# royer_DBD.net
KiCad netlist of a schematic drawn in EAGLE
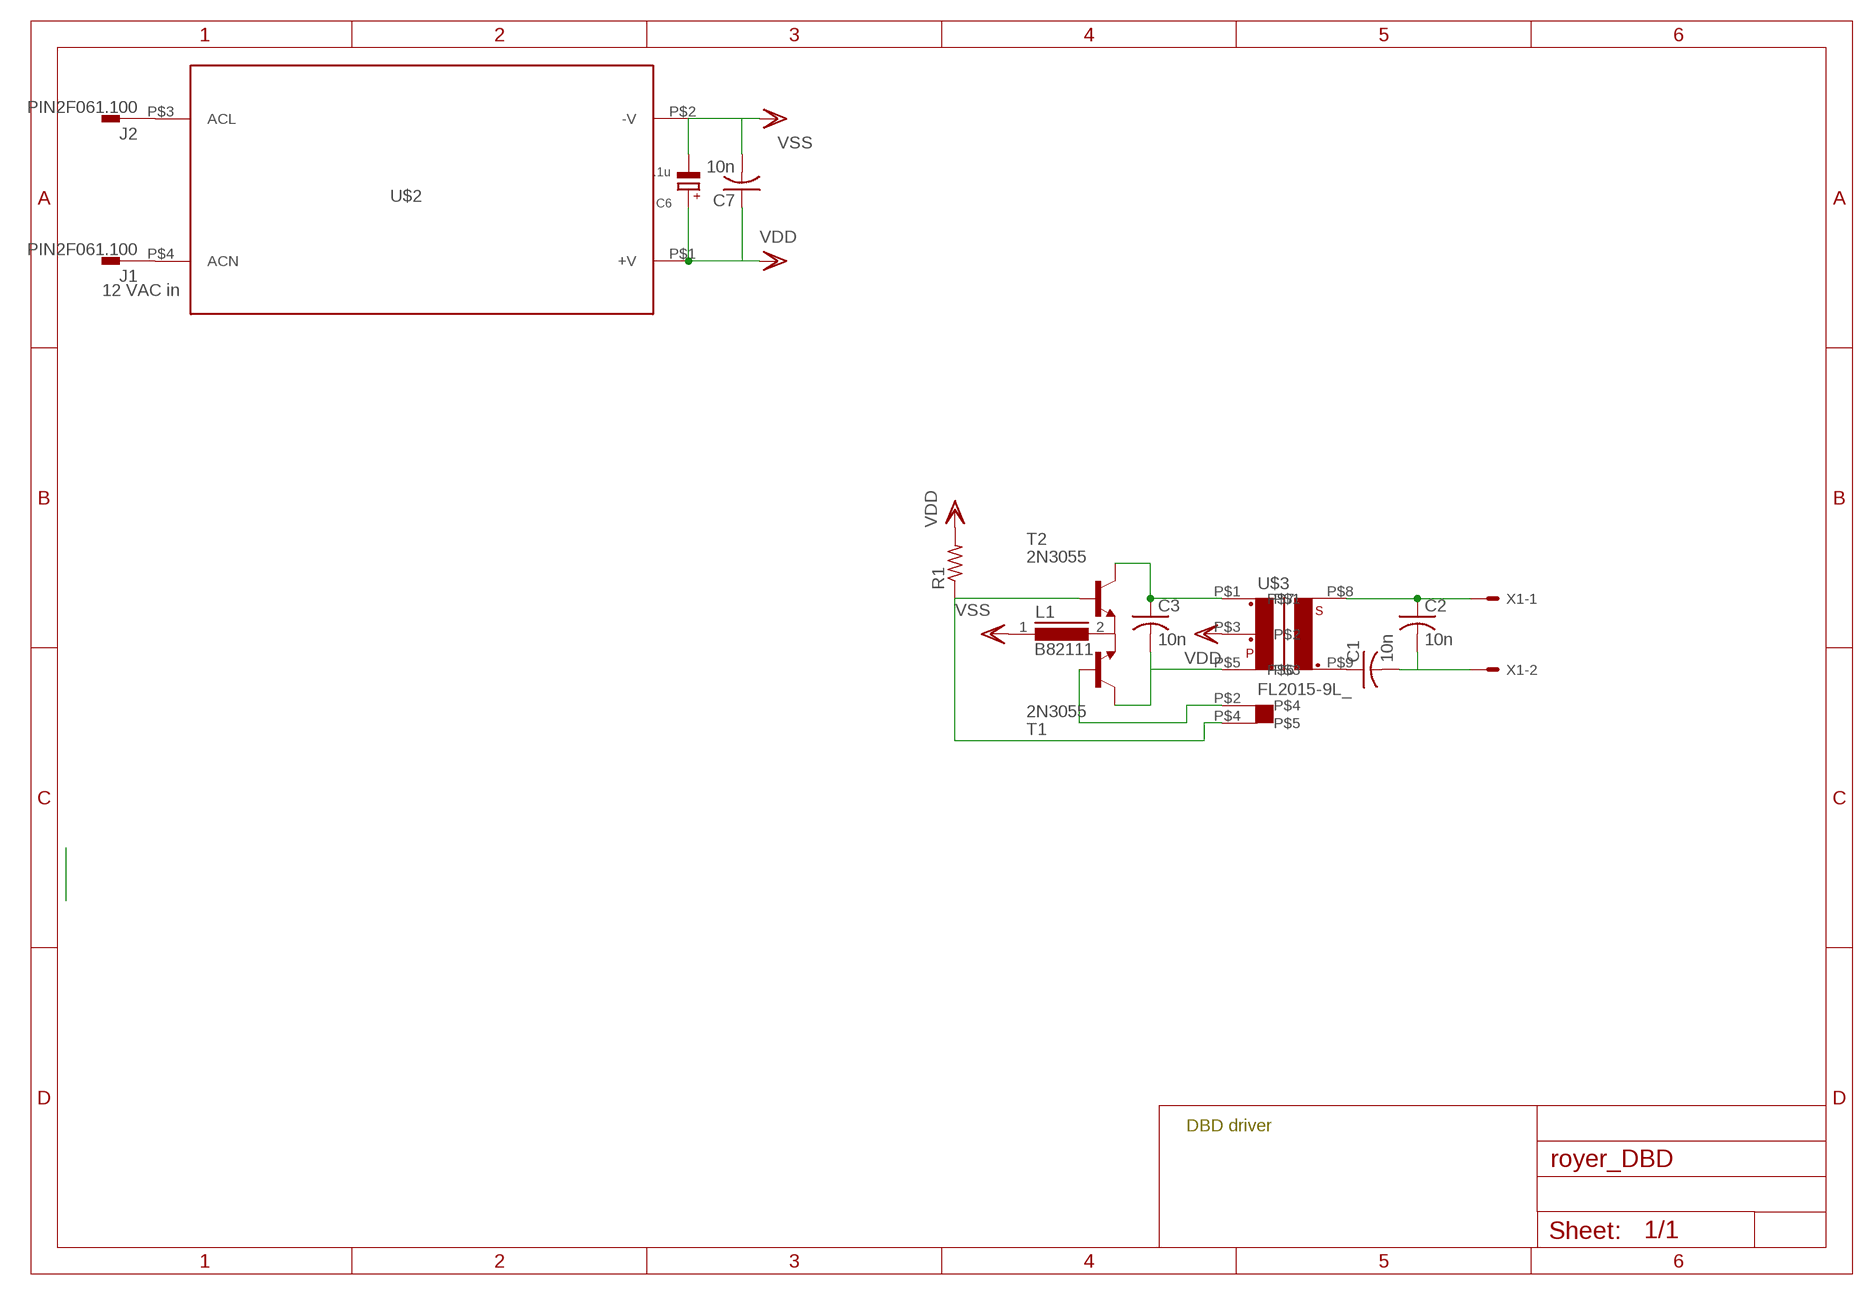
[diagram p0: schematic, sheet 1]

(export (version "E")
  (design (tool "Eeschema 10.0.6"))
  (components
    (comp (ref "C1")
      (value "10n")
      (footprint "eagle-import:C075-042X103")
      (libsource (lib "eagle-import") (part "C-US075-042X103"))
    )
    (comp (ref "C2")
      (value "10n")
      (footprint "eagle-import:C075-042X103")
      (libsource (lib "eagle-import") (part "C-US075-042X103"))
    )
    (comp (ref "C3")
      (value "10n")
      (footprint "eagle-import:C075-042X103")
      (libsource (lib "eagle-import") (part "C-US075-042X103"))
    )
    (comp (ref "C6")
      (value ".1u")
      (footprint "eagle-import:E5-8,5")
      (libsource (lib "eagle-import") (part "CPOL-EUE5-8.5"))
    )
    (comp (ref "C7")
      (value "10n")
      (footprint "eagle-import:C075-042X103")
      (libsource (lib "eagle-import") (part "C-US075-042X103"))
    )
    (comp (ref "J1")
      (value "PIN2F061.100")
      (footprint "eagle-import:F061.100")
      (libsource (lib "eagle-import") (part "PIN2F061.100"))
    )
    (comp (ref "J2")
      (value "PIN2F061.100")
      (footprint "eagle-import:F061.100")
      (libsource (lib "eagle-import") (part "PIN2F061.100"))
    )
    (comp (ref "L1")
      (value "B82111")
      (footprint "eagle-import:SUKW1-30")
      (libsource (lib "eagle-import") (part "B82111"))
    )
    (comp (ref "R1")
      (value "R-US_0207/10")
      (footprint "eagle-import:0207_10")
      (libsource (lib "eagle-import") (part "R-US_0207/10"))
    )
    (comp (ref "T1")
      (value "2N3055")
      (footprint "eagle-import:TO3")
      (libsource (lib "eagle-import") (part "2N3055"))
    )
    (comp (ref "T2")
      (value "2N3055")
      (footprint "eagle-import:TO3")
      (libsource (lib "eagle-import") (part "2N3055"))
    )
    (comp (ref "U$2")
      (value "IRM-60-12")
      (footprint "eagle-import:IRM-60-12")
      (libsource (lib "eagle-import") (part "IRM-60-12"))
    )
    (comp (ref "U$3")
      (value "FL2015-9L_")
      (footprint "eagle-import:1")
      (libsource (lib "eagle-import") (part "FL2015-9L_"))
    )
    (comp (ref "X1")
      (value "KK-156-2")
      (footprint "eagle-import:KK-156-2")
      (libsource (lib "eagle-import") (part "KK-156-2"))
    )
  )
  (nets
    (net (code "1") (name "Net-(C3-Pad1)") (class "Default")
      (node (ref "C3") (pin "1") (pinfunction "1_1") (pintype "passive"))
      (node (ref "T2") (pin "C") (pinfunction "C_C") (pintype "passive"))
      (node (ref "T2") (pin "C/") (pinfunction "C_C/") (pintype "passive"))
      (node (ref "U$3") (pin "P$1") (pinfunction "P$1_P$1") (pintype "bidirectional"))
    )
    (net (code "2") (name "Net-(L1-Pad2)") (class "Default")
      (node (ref "L1") (pin "2") (pinfunction "2_2") (pintype "passive"))
      (node (ref "T1") (pin "E") (pinfunction "E_E") (pintype "passive"))
      (node (ref "T2") (pin "E") (pinfunction "E_E") (pintype "passive"))
    )
    (net (code "3") (name "Net-(U$2-ACL)") (class "Default")
      (node (ref "J2") (pin "A1") (pinfunction "1_A1") (pintype "passive"))
      (node (ref "J2") (pin "A2") (pinfunction "1_A2") (pintype "passive"))
      (node (ref "U$2") (pin "P$3") (pinfunction "ACL_P$3") (pintype "bidirectional"))
    )
    (net (code "4") (name "Net-(U$2-ACN)") (class "Default")
      (node (ref "J1") (pin "A1") (pinfunction "1_A1") (pintype "passive"))
      (node (ref "J1") (pin "A2") (pinfunction "1_A2") (pintype "passive"))
      (node (ref "U$2") (pin "P$4") (pinfunction "ACN_P$4") (pintype "bidirectional"))
    )
    (net (code "5") (name "Net-(U$3-P$3)") (class "Default")
      (node (ref "C3") (pin "2") (pinfunction "2_2") (pintype "passive"))
      (node (ref "T1") (pin "C") (pinfunction "C_C") (pintype "passive"))
      (node (ref "T1") (pin "C/") (pinfunction "C_C/") (pintype "passive"))
      (node (ref "U$3") (pin "P$5") (pinfunction "P$3_P$5") (pintype "bidirectional"))
    )
    (net (code "6") (name "Net-(U$3-P$4)") (class "Default")
      (node (ref "T1") (pin "B") (pinfunction "B_B") (pintype "passive"))
      (node (ref "U$3") (pin "P$2") (pinfunction "P$4_P$2") (pintype "bidirectional"))
    )
    (net (code "7") (name "Net-(U$3-P$5)") (class "Default")
      (node (ref "R1") (pin "1") (pinfunction "1_1") (pintype "passive"))
      (node (ref "T2") (pin "B") (pinfunction "B_B") (pintype "passive"))
      (node (ref "U$3") (pin "P$4") (pinfunction "P$5_P$4") (pintype "bidirectional"))
    )
    (net (code "8") (name "Net-(U$3-P$6)") (class "Default")
      (node (ref "C1") (pin "1") (pinfunction "1_1") (pintype "passive"))
      (node (ref "U$3") (pin "P$9") (pinfunction "P$6_P$9") (pintype "bidirectional"))
    )
    (net (code "9") (name "Net-(U$3-P$7)") (class "Default")
      (node (ref "C2") (pin "1") (pinfunction "1_1") (pintype "passive"))
      (node (ref "U$3") (pin "P$8") (pinfunction "P$7_P$8") (pintype "bidirectional"))
      (node (ref "X1") (pin "1") (pinfunction "S_1") (pintype "passive"))
    )
    (net (code "10") (name "Net-(X1B-S)") (class "Default")
      (node (ref "C1") (pin "2") (pinfunction "2_2") (pintype "passive"))
      (node (ref "C2") (pin "2") (pinfunction "2_2") (pintype "passive"))
      (node (ref "X1") (pin "2") (pinfunction "S_2") (pintype "passive"))
    )
    (net (code "11") (name "VDD") (class "Default")
      (node (ref "C6") (pin "+") (pinfunction "+_+") (pintype "passive"))
      (node (ref "C7") (pin "1") (pinfunction "1_1") (pintype "passive"))
      (node (ref "R1") (pin "2") (pinfunction "2_2") (pintype "passive"))
      (node (ref "U$2") (pin "P$1") (pinfunction "+V_P$1") (pintype "bidirectional"))
      (node (ref "U$3") (pin "P$3") (pinfunction "P$2_P$3") (pintype "bidirectional"))
    )
    (net (code "12") (name "VSS") (class "Default")
      (node (ref "C6") (pin "-") (pinfunction "-_-") (pintype "passive"))
      (node (ref "C7") (pin "2") (pinfunction "2_2") (pintype "passive"))
      (node (ref "L1") (pin "1") (pinfunction "1_1") (pintype "passive"))
      (node (ref "U$2") (pin "P$2") (pinfunction "-V_P$2") (pintype "bidirectional"))
    )
  )
)
